# lion-battery-protection-circuit.net
KiCad netlist of a schematic drawn in Altium Designer
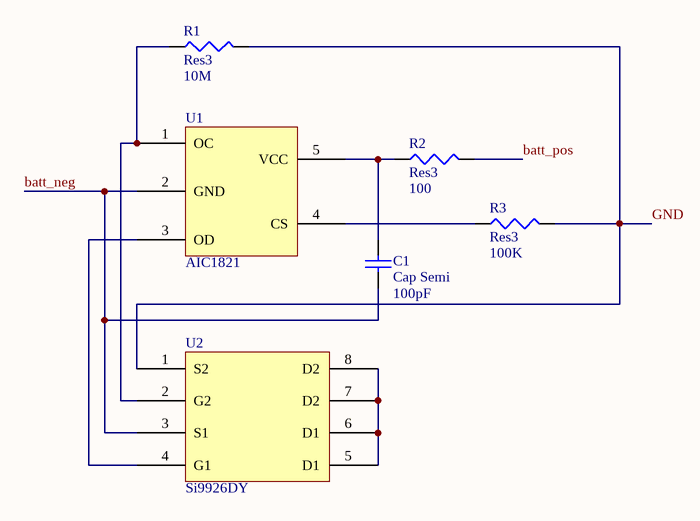
[diagram p0: lion-battery-protection-circuit.SchDoc]

(export (version "E")
  (design (tool "Eeschema 10.0.6"))
  (components
    (comp (ref "C1")
      (value "Cap Semi")
      (footprint "CAPC1005M")
      (description "LMK105BJ104KV-F")
      (fields (field (name "ALTIUM_VALUE") "100pF") (field (name "PUBLISHER") "Altium Limited"))
      (libsource (lib "Miscellaneous Devices") (part "Cap Semi"))
    )
    (comp (ref "R1")
      (value "Res3")
      (footprint "RESC1608M")
      (description "ERJ-3GEYJ106V")
      (fields (field (name "ALTIUM_VALUE") "10M") (field (name "PUBLISHER") "Altium Limited"))
      (libsource (lib "Miscellaneous Devices") (part "Res3"))
    )
    (comp (ref "R2")
      (value "Res3")
      (footprint "RESC1608M")
      (description "ERJ-3GEYJ101V")
      (fields (field (name "ALTIUM_VALUE") "100") (field (name "PUBLISHER") "Altium Limited"))
      (libsource (lib "Miscellaneous Devices") (part "Res3"))
    )
    (comp (ref "R3")
      (value "Res3")
      (footprint "RESC1608M")
      (description "ERJ-3GEYJ104V")
      (fields (field (name "ALTIUM_VALUE") "100K") (field (name "PUBLISHER") "Altium Limited"))
      (libsource (lib "Miscellaneous Devices") (part "Res3"))
    )
    (comp (ref "U1")
      (value "AIC1821")
      (footprint "SOT23-5AN")
      (description "lithium ion cell protection IC")
      (libsource (lib "AIC1821 schematic lib") (part "Component_1"))
    )
    (comp (ref "U2")
      (value "Si9926DY")
      (footprint "SOIC127P600-8BL")
      (description "dual n channel mosfets")
      (libsource (lib "Si9926 schematic lib") (part "Component_1"))
    )
  )
  (nets
    (net (code "1") (name "/GND") (class "Default")
      (node (ref "R1") (pin "2") (pinfunction "2_2") (pintype "passive"))
      (node (ref "R3") (pin "2") (pinfunction "2_2") (pintype "passive"))
      (node (ref "U2") (pin "1") (pinfunction "S2_1") (pintype "passive"))
    )
    (net (code "2") (name "/batt_neg") (class "Default")
      (node (ref "C1") (pin "1") (pinfunction "1_1") (pintype "passive"))
      (node (ref "U1") (pin "2") (pinfunction "GND_2") (pintype "power_in"))
      (node (ref "U2") (pin "3") (pinfunction "S1_3") (pintype "passive"))
    )
    (net (code "3") (name "/batt_pos") (class "Default")
      (node (ref "R2") (pin "2") (pinfunction "2_2") (pintype "passive"))
    )
    (net (code "4") (name "Net-(U1-CS)") (class "Default")
      (node (ref "R3") (pin "1") (pinfunction "1_1") (pintype "passive"))
      (node (ref "U1") (pin "4") (pinfunction "CS_4") (pintype "passive"))
    )
    (net (code "5") (name "Net-(U1-OC)") (class "Default")
      (node (ref "R1") (pin "1") (pinfunction "1_1") (pintype "passive"))
      (node (ref "U1") (pin "1") (pinfunction "OC_1") (pintype "passive"))
      (node (ref "U2") (pin "2") (pinfunction "G2_2") (pintype "passive"))
    )
    (net (code "6") (name "Net-(U1-OD)") (class "Default")
      (node (ref "U1") (pin "3") (pinfunction "OD_3") (pintype "passive"))
      (node (ref "U2") (pin "4") (pinfunction "G1_4") (pintype "passive"))
    )
    (net (code "7") (name "Net-(U1-VCC)") (class "Default")
      (node (ref "C1") (pin "2") (pinfunction "2_2") (pintype "passive"))
      (node (ref "R2") (pin "1") (pinfunction "1_1") (pintype "passive"))
      (node (ref "U1") (pin "5") (pinfunction "VCC_5") (pintype "power_in"))
    )
    (net (code "8") (name "Net-(U2-D1-Pad5)") (class "Default")
      (node (ref "U2") (pin "5") (pinfunction "D1_5") (pintype "passive"))
      (node (ref "U2") (pin "6") (pinfunction "D1_6") (pintype "passive"))
      (node (ref "U2") (pin "7") (pinfunction "D2_7") (pintype "passive"))
      (node (ref "U2") (pin "8") (pinfunction "D2_8") (pintype "passive"))
    )
  )
)
